# PIXRACER-POWER-R12.net
KiCad netlist of a schematic drawn in Altium Designer
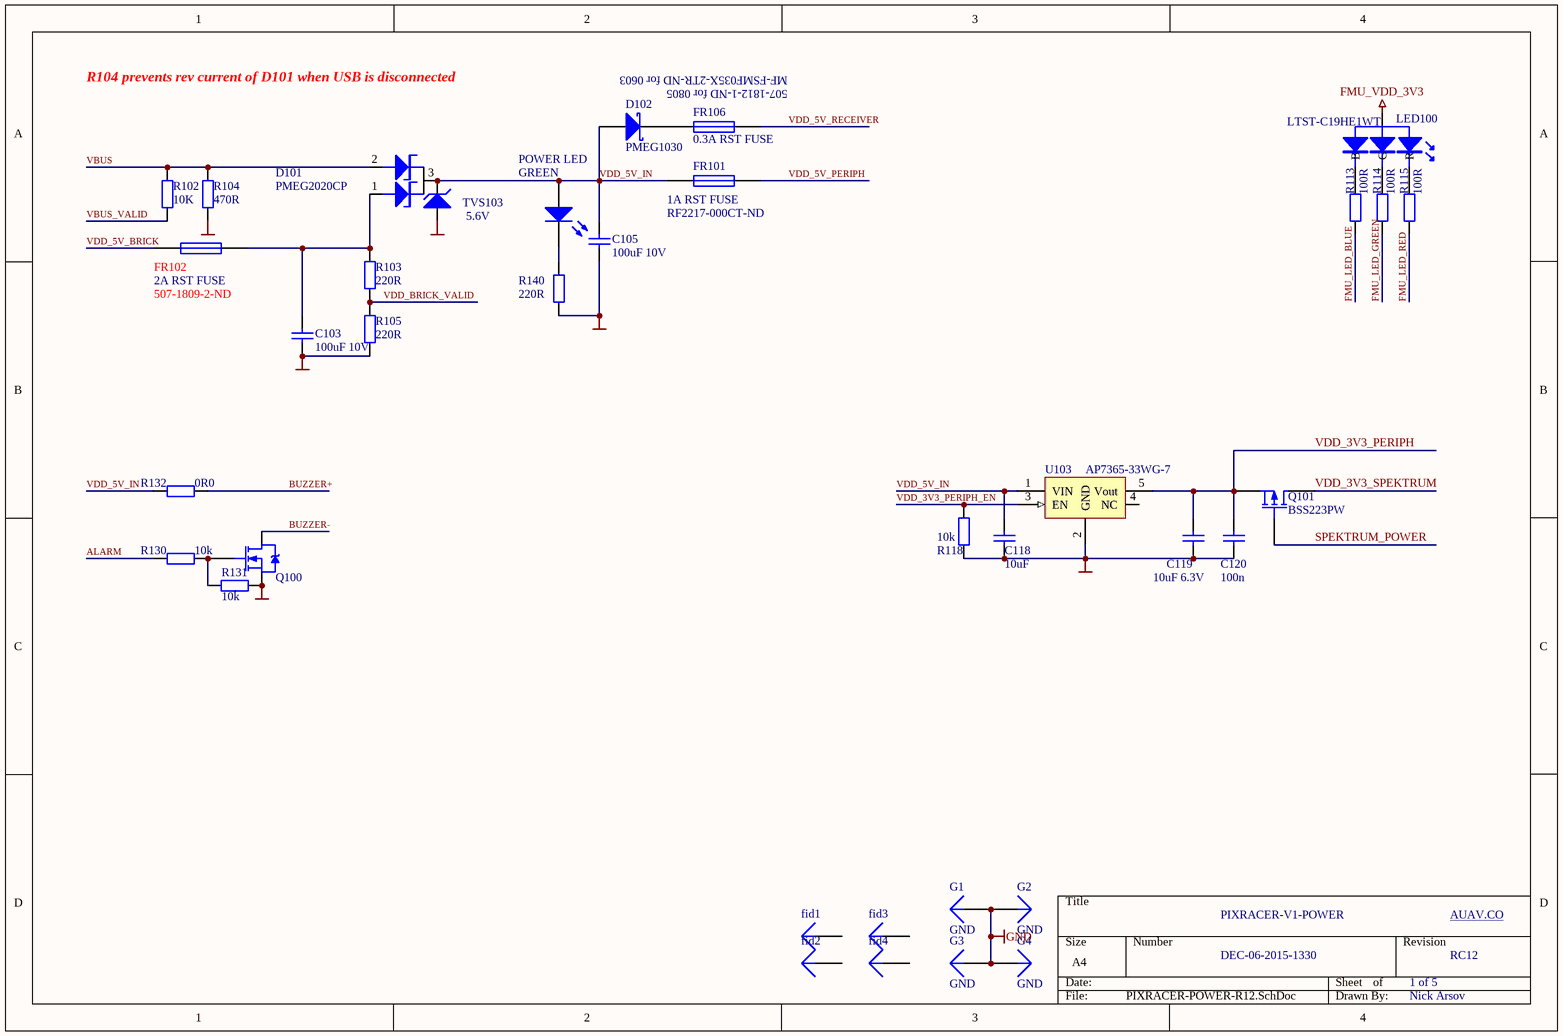
[diagram p0: PIXRACER-POWER-R12.SchDoc]

(export (version "E")
  (design (tool "Eeschema 10.0.6"))
  (components
    (comp (ref "C103")
      (value "100uF 10V")
      (footprint "0805A")
      (description "Capacitor")
      (fields (field (name "PUBLISHER") "Altium Limited"))
      (libsource (lib "Miscellaneous Devices") (part "Cap"))
    )
    (comp (ref "C105")
      (value "100uF 10V")
      (footprint "0805A")
      (description "Capacitor")
      (fields (field (name "PUBLISHER") "Altium Limited"))
      (libsource (lib "Miscellaneous Devices") (part "Cap"))
    )
    (comp (ref "C118")
      (value "10uF")
      (footprint "0603A")
      (description "Capacitor")
      (fields (field (name "PUBLISHER") "Altium Limited"))
      (libsource (lib "Miscellaneous Devices") (part "Cap"))
    )
    (comp (ref "C119")
      (value "10uF 6.3V")
      (footprint "0603A")
      (description "Capacitor")
      (fields (field (name "PUBLISHER") "Altium Limited"))
      (libsource (lib "Miscellaneous Devices") (part "Cap"))
    )
    (comp (ref "C120")
      (value "100n")
      (footprint "0603A")
      (description "Capacitor")
      (fields (field (name "PUBLISHER") "Altium Limited"))
      (libsource (lib "Miscellaneous Devices") (part "Cap"))
    )
    (comp (ref "D101")
      (value "PMEG2020CP")
      (footprint "pmeg2020cp")
      (libsource (lib "My_Altium") (part "PMEG2020CP"))
    )
    (comp (ref "D102")
      (value "PMEG1030")
      (footprint "sod323f")
      (description "Schottky Diode")
      (fields (field (name "PUBLISHER") "Altium Limited"))
      (libsource (lib "Miscellaneous Devices") (part "D Schottky"))
    )
    (comp (ref "fid1")
      (value "~")
      (footprint "SMT_PAD")
      (description "Plug")
      (fields (field (name "PUBLISHER") "Altium Limited"))
      (libsource (lib "Miscellaneous Connectors") (part "Plug"))
    )
    (comp (ref "fid2")
      (value "~")
      (footprint "SMT_PAD")
      (description "Plug")
      (fields (field (name "PUBLISHER") "Altium Limited"))
      (libsource (lib "Miscellaneous Connectors") (part "Plug"))
    )
    (comp (ref "fid3")
      (value "~")
      (footprint "SMT_PAD")
      (description "Plug")
      (fields (field (name "PUBLISHER") "Altium Limited"))
      (libsource (lib "Miscellaneous Connectors") (part "Plug"))
    )
    (comp (ref "fid4")
      (value "~")
      (footprint "SMT_PAD")
      (description "Plug")
      (fields (field (name "PUBLISHER") "Altium Limited"))
      (libsource (lib "Miscellaneous Connectors") (part "Plug"))
    )
    (comp (ref "FR101")
      (value "1A RST FUSE")
      (footprint "0805A")
      (description "Fuse")
      (fields (field (name "DIGIKEY") "RF2217-000CT-ND") (field (name "PUBLISHER") "Altium Limited"))
      (libsource (lib "Miscellaneous Devices") (part "Fuse 1"))
    )
    (comp (ref "FR102")
      (value "2A RST FUSE")
      (footprint "1206A")
      (description "Fuse")
      (fields (field (name "DIGIKEY") "507-1809-2-ND") (field (name "PUBLISHER") "Altium Limited"))
      (libsource (lib "Miscellaneous Devices") (part "Fuse 1"))
    )
    (comp (ref "FR106")
      (value "0.3A RST FUSE")
      (footprint "0805A")
      (description "Fuse")
      (fields (field (name "PUBLISHER") "Altium Limited"))
      (libsource (lib "Miscellaneous Devices") (part "Fuse 1"))
    )
    (comp (ref "G1")
      (value "GND")
      (description "Plug")
      (fields (field (name "PUBLISHER") "Altium Limited"))
      (libsource (lib "Miscellaneous Connectors") (part "Plug"))
    )
    (comp (ref "G2")
      (value "GND")
      (description "Plug")
      (fields (field (name "PUBLISHER") "Altium Limited"))
      (libsource (lib "Miscellaneous Connectors") (part "Plug"))
    )
    (comp (ref "G3")
      (value "GND")
      (description "Plug")
      (fields (field (name "PUBLISHER") "Altium Limited"))
      (libsource (lib "Miscellaneous Connectors") (part "Plug"))
    )
    (comp (ref "G4")
      (value "GND")
      (description "Plug")
      (fields (field (name "PUBLISHER") "Altium Limited"))
      (libsource (lib "Miscellaneous Connectors") (part "Plug"))
    )
    (comp (ref "LED100")
      (value "LTST-C19HE1WT")
      (footprint "LTST-C19HE1WT")
      (libsource (lib "My_Altium") (part "RGB_LED_5MM"))
    )
    (comp (ref "POWER LED")
      (value "GREEN")
      (footprint "0603A")
      (description "Typical INFRARED GaAs LED")
      (fields (field (name "PUBLISHER") "Altium Limited"))
      (libsource (lib "Miscellaneous Devices") (part "LED0"))
    )
    (comp (ref "Q100")
      (value "DMG1012UW")
      (footprint "2N7002-SOT323")
      (description "N-Channel Power MOSFET")
      (fields (field (name "PUBLISHER") "Altium Limited"))
      (libsource (lib "Miscellaneous Devices") (part "NMOS-2"))
    )
    (comp (ref "Q101")
      (value "BSS223PW")
      (footprint "2N7002-SOT323")
      (description "P-Channel MOSFET")
      (fields (field (name "PUBLISHER") "Altium Limited"))
      (libsource (lib "Miscellaneous Devices") (part "MOSFET-P"))
    )
    (comp (ref "R102")
      (value "10K")
      (footprint "0603A")
      (description "Resistor")
      (fields (field (name "PUBLISHER") "Altium Limited"))
      (libsource (lib "") (part "Res2_1"))
    )
    (comp (ref "R103")
      (value "220R")
      (footprint "0603A")
      (description "Resistor")
      (fields (field (name "PUBLISHER") "Altium Limited"))
      (libsource (lib "Miscellaneous Devices") (part "Res2"))
    )
    (comp (ref "R104")
      (value "470R")
      (footprint "0603A")
      (description "Resistor")
      (fields (field (name "PUBLISHER") "Altium Limited"))
      (libsource (lib "") (part "Res2_1"))
    )
    (comp (ref "R105")
      (value "220R")
      (footprint "0603A")
      (description "Resistor")
      (fields (field (name "PUBLISHER") "Altium Limited"))
      (libsource (lib "Miscellaneous Devices") (part "Res2"))
    )
    (comp (ref "R113")
      (value "100R")
      (footprint "0402A")
      (description "Resistor")
      (fields (field (name "PUBLISHER") "Altium Limited"))
      (libsource (lib "") (part "Res2_1"))
    )
    (comp (ref "R114")
      (value "100R")
      (footprint "0402A")
      (description "Resistor")
      (fields (field (name "PUBLISHER") "Altium Limited"))
      (libsource (lib "") (part "Res2_1"))
    )
    (comp (ref "R115")
      (value "100R")
      (footprint "0402A")
      (description "Resistor")
      (fields (field (name "PUBLISHER") "Altium Limited"))
      (libsource (lib "") (part "Res2_1"))
    )
    (comp (ref "R118")
      (value "10k")
      (footprint "0603A")
      (description "Resistor")
      (fields (field (name "PUBLISHER") "Altium Limited"))
      (libsource (lib "") (part "Res2_1"))
    )
    (comp (ref "R130")
      (value "10k")
      (footprint "0402A")
      (description "Resistor")
      (fields (field (name "PUBLISHER") "Altium Limited"))
      (libsource (lib "") (part "Res2_2"))
    )
    (comp (ref "R131")
      (value "10k")
      (footprint "0402A")
      (description "Resistor")
      (fields (field (name "PUBLISHER") "Altium Limited"))
      (libsource (lib "") (part "Res2_3"))
    )
    (comp (ref "R132")
      (value "0R0")
      (footprint "0402A")
      (description "Resistor")
      (fields (field (name "PUBLISHER") "Altium Limited"))
      (libsource (lib "") (part "Res2_2"))
    )
    (comp (ref "R140")
      (value "220R")
      (footprint "0603A")
      (description "Resistor")
      (fields (field (name "PUBLISHER") "Altium Limited"))
      (libsource (lib "") (part "Res2_1"))
    )
    (comp (ref "TVS103")
      (value "5.6V")
      (footprint "SOD123F")
      (description "Zener Diode")
      (fields (field (name "PUBLISHER") "Altium Limited"))
      (libsource (lib "Miscellaneous Devices") (part "D Zener"))
    )
    (comp (ref "U103")
      (value "AP7365-33WG-7")
      (footprint "SOT23-5")
      (libsource (lib "My_Altium") (part "LP5907-Q1"))
    )
  )
  (nets
    (net (code "1") (name "/ALARM") (class "Default")
      (node (ref "R130") (pin "2") (pinfunction "2_2") (pintype "passive"))
    )
    (net (code "2") (name "/BUZZER+") (class "Default")
      (node (ref "R132") (pin "1") (pinfunction "1_1") (pintype "passive"))
    )
    (net (code "3") (name "/BUZZER-") (class "Default")
      (node (ref "Q100") (pin "1") (pinfunction "D_1") (pintype "passive"))
    )
    (net (code "4") (name "/FMU_LED_BLUE") (class "Default")
      (node (ref "R113") (pin "1") (pinfunction "1_1") (pintype "passive"))
    )
    (net (code "5") (name "/FMU_LED_GREEN") (class "Default")
      (node (ref "R114") (pin "1") (pinfunction "1_1") (pintype "passive"))
    )
    (net (code "6") (name "/FMU_LED_RED") (class "Default")
      (node (ref "R115") (pin "1") (pinfunction "1_1") (pintype "passive"))
    )
    (net (code "7") (name "/SPEKTRUM_POWER") (class "Default")
      (node (ref "Q101") (pin "3") (pinfunction "G_3") (pintype "passive"))
    )
    (net (code "8") (name "/VBUS") (class "Default")
      (node (ref "D101") (pin "2") (pintype "passive"))
      (node (ref "R102") (pin "2") (pinfunction "2_2") (pintype "passive"))
      (node (ref "R104") (pin "2") (pinfunction "2_2") (pintype "passive"))
    )
    (net (code "9") (name "/VBUS_VALID") (class "Default")
      (node (ref "R102") (pin "1") (pinfunction "1_1") (pintype "passive"))
    )
    (net (code "10") (name "/VDD_3V3_PERIPH") (class "Default")
      (node (ref "C119") (pin "2") (pinfunction "2_2") (pintype "passive"))
      (node (ref "C120") (pin "2") (pinfunction "2_2") (pintype "passive"))
      (node (ref "Q101") (pin "2") (pinfunction "S_2") (pintype "passive"))
      (node (ref "U103") (pin "5") (pinfunction "Vout_5") (pintype "power_in"))
    )
    (net (code "11") (name "/VDD_3V3_PERIPH_EN") (class "Default")
      (node (ref "R118") (pin "2") (pinfunction "2_2") (pintype "passive"))
      (node (ref "U103") (pin "3") (pinfunction "EN_3") (pintype "input"))
    )
    (net (code "12") (name "/VDD_3V3_SPEKTRUM") (class "Default")
      (node (ref "Q101") (pin "1") (pinfunction "D_1") (pintype "passive"))
    )
    (net (code "13") (name "/VDD_5V_BRICK") (class "Default")
      (node (ref "FR102") (pin "1") (pinfunction "1_1") (pintype "passive"))
    )
    (net (code "14") (name "/VDD_5V_IN") (class "Default")
      (node (ref "C105") (pin "2") (pinfunction "2_2") (pintype "passive"))
      (node (ref "C118") (pin "2") (pinfunction "2_2") (pintype "passive"))
      (node (ref "D101") (pin "3") (pintype "passive"))
      (node (ref "D102") (pin "1") (pinfunction "A_1") (pintype "passive"))
      (node (ref "FR101") (pin "1") (pinfunction "1_1") (pintype "passive"))
      (node (ref "POWER LED") (pin "1") (pinfunction "A_1") (pintype "passive"))
      (node (ref "R132") (pin "2") (pinfunction "2_2") (pintype "passive"))
      (node (ref "TVS103") (pin "2") (pinfunction "K_2") (pintype "passive"))
      (node (ref "U103") (pin "1") (pinfunction "VIN_1") (pintype "power_in"))
    )
    (net (code "15") (name "/VDD_5V_PERIPH") (class "Default")
      (node (ref "FR101") (pin "2") (pinfunction "2_2") (pintype "passive"))
    )
    (net (code "16") (name "/VDD_5V_RECEIVER") (class "Default")
      (node (ref "FR106") (pin "2") (pinfunction "2_2") (pintype "passive"))
    )
    (net (code "17") (name "/VDD_BRICK_VALID") (class "Default")
      (node (ref "R103") (pin "2") (pinfunction "2_2") (pintype "passive"))
      (node (ref "R105") (pin "1") (pinfunction "1_1") (pintype "passive"))
    )
    (net (code "18") (name "FMU_VDD_3V3") (class "Default")
      (node (ref "LED100") (pin "4") (pinfunction "A_4") (pintype "passive"))
    )
    (net (code "19") (name "GND") (class "Default")
      (node (ref "C103") (pin "1") (pinfunction "1_1") (pintype "passive"))
      (node (ref "C105") (pin "1") (pinfunction "1_1") (pintype "passive"))
      (node (ref "C118") (pin "1") (pinfunction "1_1") (pintype "passive"))
      (node (ref "C119") (pin "1") (pinfunction "1_1") (pintype "passive"))
      (node (ref "C120") (pin "1") (pinfunction "1_1") (pintype "passive"))
      (node (ref "G1") (pin "1") (pinfunction "1_1") (pintype "passive"))
      (node (ref "G2") (pin "1") (pinfunction "1_1") (pintype "passive"))
      (node (ref "G3") (pin "1") (pinfunction "1_1") (pintype "passive"))
      (node (ref "G4") (pin "1") (pinfunction "1_1") (pintype "passive"))
      (node (ref "Q100") (pin "2") (pinfunction "S_2") (pintype "passive"))
      (node (ref "R104") (pin "1") (pinfunction "1_1") (pintype "passive"))
      (node (ref "R105") (pin "2") (pinfunction "2_2") (pintype "passive"))
      (node (ref "R118") (pin "1") (pinfunction "1_1") (pintype "passive"))
      (node (ref "R131") (pin "2") (pinfunction "2_2") (pintype "passive"))
      (node (ref "R140") (pin "1") (pinfunction "1_1") (pintype "passive"))
      (node (ref "TVS103") (pin "1") (pinfunction "A_1") (pintype "passive"))
      (node (ref "U103") (pin "2") (pinfunction "GND_2") (pintype "power_in"))
    )
    (net (code "20") (name "Net-(C103-Pad2)") (class "Default")
      (node (ref "C103") (pin "2") (pinfunction "2_2") (pintype "passive"))
      (node (ref "D101") (pin "1") (pintype "passive"))
      (node (ref "FR102") (pin "2") (pinfunction "2_2") (pintype "passive"))
      (node (ref "R103") (pin "1") (pinfunction "1_1") (pintype "passive"))
    )
    (net (code "21") (name "Net-(D102-K)") (class "Default")
      (node (ref "D102") (pin "2") (pinfunction "K_2") (pintype "passive"))
      (node (ref "FR106") (pin "1") (pinfunction "1_1") (pintype "passive"))
    )
    (net (code "22") (name "Net-(LED100-B)") (class "Default")
      (node (ref "LED100") (pin "3") (pinfunction "B_3") (pintype "passive"))
      (node (ref "R113") (pin "2") (pinfunction "2_2") (pintype "passive"))
    )
    (net (code "23") (name "Net-(LED100-G)") (class "Default")
      (node (ref "LED100") (pin "2") (pinfunction "G_2") (pintype "passive"))
      (node (ref "R114") (pin "2") (pinfunction "2_2") (pintype "passive"))
    )
    (net (code "24") (name "Net-(LED100-R)") (class "Default")
      (node (ref "LED100") (pin "1") (pinfunction "R_1") (pintype "passive"))
      (node (ref "R115") (pin "2") (pinfunction "2_2") (pintype "passive"))
    )
    (net (code "25") (name "Net-(POWER LED-K)") (class "Default")
      (node (ref "POWER LED") (pin "2") (pinfunction "K_2") (pintype "passive"))
      (node (ref "R140") (pin "2") (pinfunction "2_2") (pintype "passive"))
    )
    (net (code "26") (name "Net-(Q100-G)") (class "Default")
      (node (ref "Q100") (pin "3") (pinfunction "G_3") (pintype "passive"))
      (node (ref "R130") (pin "1") (pinfunction "1_1") (pintype "passive"))
      (node (ref "R131") (pin "1") (pinfunction "1_1") (pintype "passive"))
    )
    (net (code "27") (name "unconnected-(U103-NC-Pad4)") (class "Default")
      (node (ref "U103") (pin "4") (pinfunction "NC_4") (pintype "passive"))
    )
    (net (code "28") (name "unconnected-(fid1-Pad1)") (class "Default")
      (node (ref "fid1") (pin "1") (pinfunction "1_1") (pintype "passive"))
    )
    (net (code "29") (name "unconnected-(fid2-Pad1)") (class "Default")
      (node (ref "fid2") (pin "1") (pinfunction "1_1") (pintype "passive"))
    )
    (net (code "30") (name "unconnected-(fid3-Pad1)") (class "Default")
      (node (ref "fid3") (pin "1") (pinfunction "1_1") (pintype "passive"))
    )
    (net (code "31") (name "unconnected-(fid4-Pad1)") (class "Default")
      (node (ref "fid4") (pin "1") (pinfunction "1_1") (pintype "passive"))
    )
  )
)
